# Schaltplan_Vier-Gewinnt.net
KiCad netlist of a schematic drawn in EasyEDA
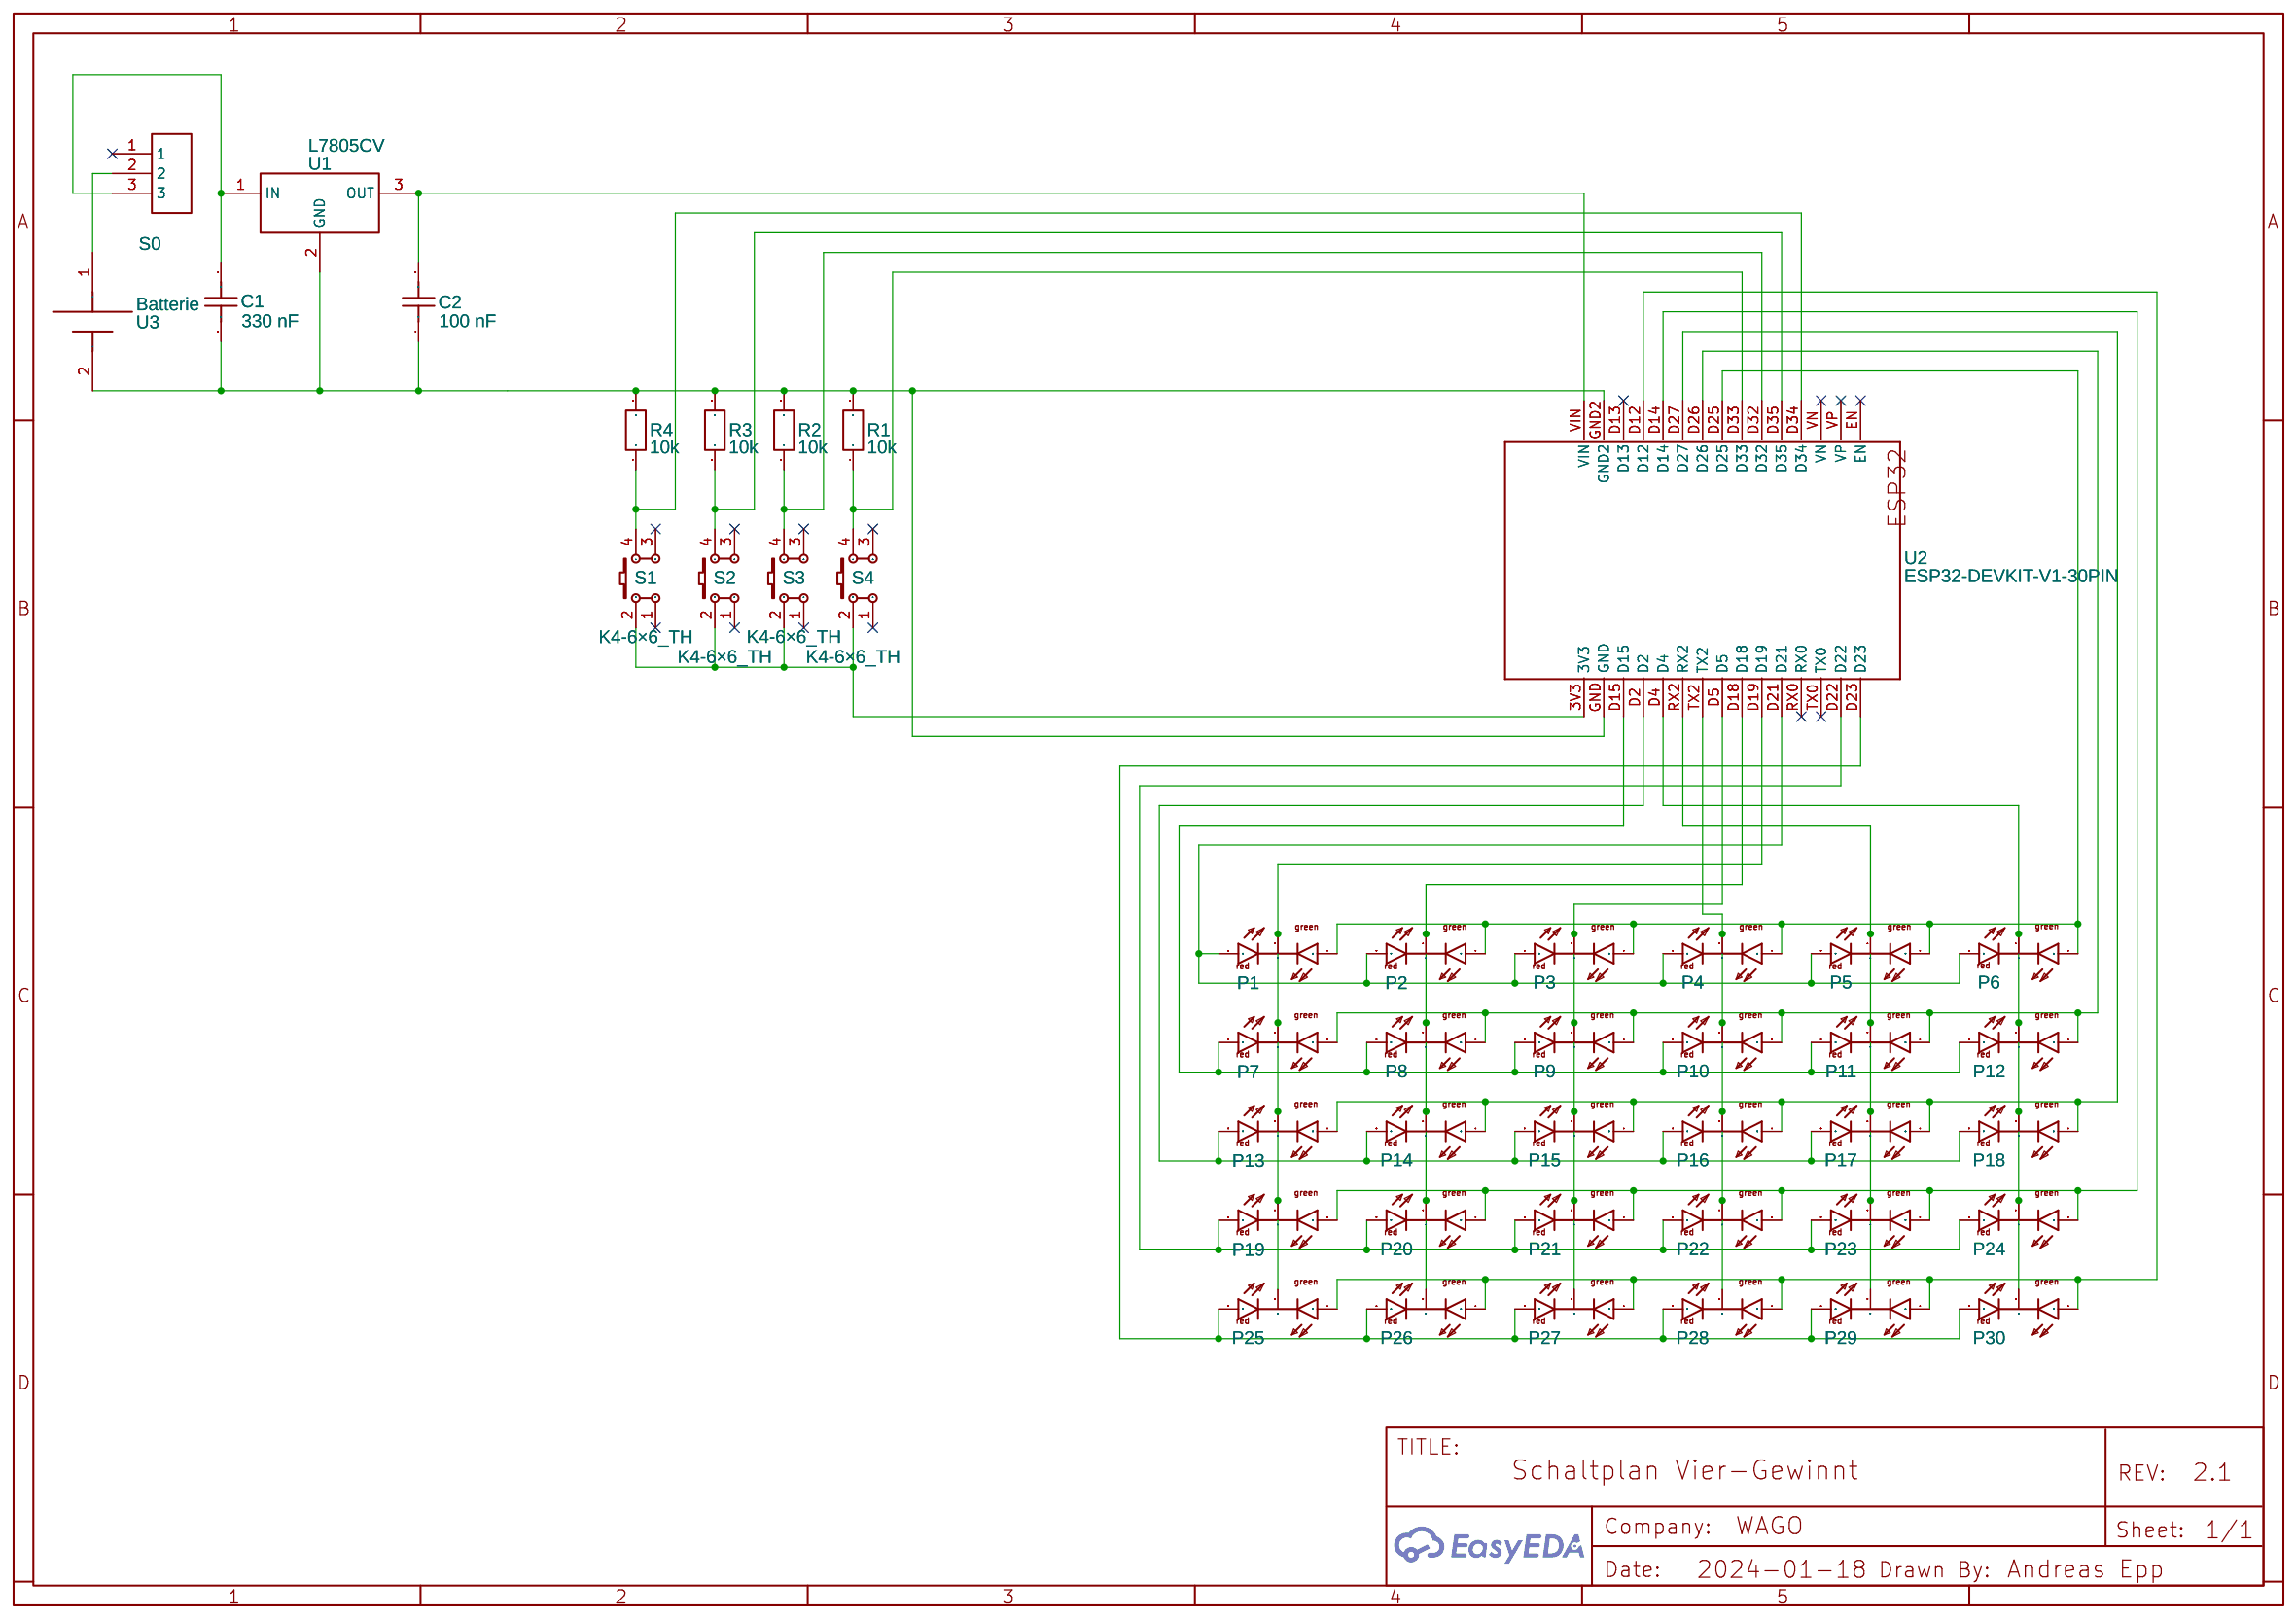
[diagram p0: schematic sheet]

(export (version "E")
  (design (tool "Eeschema 10.0.6"))
  (components
    (comp (ref "C1") (value "330 nF") (libsource (lib "") (part "C_RAD-0.1_US")))
    (comp (ref "C2")
      (value "100 nF")
      (fields (field (name "Manufacturer Part") "B32529C0104M289") (field (name "Manufacturer") "TDK"))
      (libsource (lib "") (part "B32529C0104M289"))
    )
    (comp (ref "P1") (value "NO") (libsource (lib "") (part "DUOLED-RG-C_1")))
    (comp (ref "P2") (value "NO") (libsource (lib "") (part "DUOLED-RG-C_1")))
    (comp (ref "P3") (value "NO") (libsource (lib "") (part "DUOLED-RG-C_1")))
    (comp (ref "P4") (value "NO") (libsource (lib "") (part "DUOLED-RG-C_1")))
    (comp (ref "P5") (value "NO") (libsource (lib "") (part "DUOLED-RG-C_1")))
    (comp (ref "P6") (value "NO") (libsource (lib "") (part "DUOLED-RG-C")))
    (comp (ref "P7") (value "NO") (libsource (lib "") (part "DUOLED-RG-C")))
    (comp (ref "P8") (value "NO") (libsource (lib "") (part "DUOLED-RG-C")))
    (comp (ref "P9") (value "NO") (libsource (lib "") (part "DUOLED-RG-C")))
    (comp (ref "P10") (value "NO") (libsource (lib "") (part "DUOLED-RG-C")))
    (comp (ref "P11") (value "NO") (libsource (lib "") (part "DUOLED-RG-C")))
    (comp (ref "P12") (value "NO") (libsource (lib "") (part "DUOLED-RG-C")))
    (comp (ref "P13") (value "NO") (libsource (lib "") (part "DUOLED-RG-C")))
    (comp (ref "P14") (value "NO") (libsource (lib "") (part "DUOLED-RG-C")))
    (comp (ref "P15") (value "NO") (libsource (lib "") (part "DUOLED-RG-C")))
    (comp (ref "P16") (value "NO") (libsource (lib "") (part "DUOLED-RG-C")))
    (comp (ref "P17") (value "NO") (libsource (lib "") (part "DUOLED-RG-C")))
    (comp (ref "P18") (value "NO") (libsource (lib "") (part "DUOLED-RG-C")))
    (comp (ref "P19") (value "NO") (libsource (lib "") (part "DUOLED-RG-C")))
    (comp (ref "P20") (value "NO") (libsource (lib "") (part "DUOLED-RG-C")))
    (comp (ref "P21") (value "NO") (libsource (lib "") (part "DUOLED-RG-C")))
    (comp (ref "P22") (value "NO") (libsource (lib "") (part "DUOLED-RG-C")))
    (comp (ref "P23") (value "NO") (libsource (lib "") (part "DUOLED-RG-C")))
    (comp (ref "P24") (value "NO") (libsource (lib "") (part "DUOLED-RG-C")))
    (comp (ref "P25") (value "NO") (libsource (lib "") (part "DUOLED-RG-C")))
    (comp (ref "P26") (value "NO") (libsource (lib "") (part "DUOLED-RG-C")))
    (comp (ref "P27") (value "NO") (libsource (lib "") (part "DUOLED-RG-C")))
    (comp (ref "P28") (value "NO") (libsource (lib "") (part "DUOLED-RG-C")))
    (comp (ref "P29") (value "NO") (libsource (lib "") (part "DUOLED-RG-C")))
    (comp (ref "P30") (value "NO") (libsource (lib "") (part "DUOLED-RG-C")))
    (comp (ref "R1") (value "10k") (libsource (lib "") (part "R_AXIAL-0.3_EU")))
    (comp (ref "R2") (value "10k") (libsource (lib "") (part "R_AXIAL-0.3_EU")))
    (comp (ref "R3") (value "10k") (libsource (lib "") (part "R_AXIAL-0.3_EU")))
    (comp (ref "R4") (value "10k") (libsource (lib "") (part "R_AXIAL-0.3_EU")))
    (comp (ref "S0") (value "NO") (libsource (lib "") (part "CSS-1201")))
    (comp (ref "S1")
      (value "K4-6×6_TH")
      (fields (field (name "Manufacturer Part") "K2-1102DP-E4SW-04") (field (name "Manufacturer") "韩国韩荣"))
      (libsource (lib "") (part "K4-6×6_TH"))
    )
    (comp (ref "S2")
      (value "K4-6×6_TH")
      (fields (field (name "Manufacturer Part") "K2-1102DP-E4SW-04") (field (name "Manufacturer") "韩国韩荣"))
      (libsource (lib "") (part "K4-6×6_TH"))
    )
    (comp (ref "S3")
      (value "K4-6×6_TH")
      (fields (field (name "Manufacturer Part") "K2-1102DP-E4SW-04") (field (name "Manufacturer") "韩国韩荣"))
      (libsource (lib "") (part "K4-6×6_TH"))
    )
    (comp (ref "S4")
      (value "K4-6×6_TH")
      (fields (field (name "Manufacturer Part") "K2-1102DP-E4SW-04") (field (name "Manufacturer") "韩国韩荣"))
      (libsource (lib "") (part "K4-6×6_TH"))
    )
    (comp (ref "U1")
      (value "L7805CV")
      (fields (field (name "Manufacturer") "STMicroelectronics"))
      (libsource (lib "") (part "L7805CV"))
    )
    (comp (ref "U2") (value "ESP32-DEVKIT-V1-30PIN") (libsource (lib "") (part "ESP32-DEVKIT-V1-30PIN")))
    (comp (ref "U3") (value "Batterie") (libsource (lib "") (part "Batterie")))
  )
  (nets
    (net (code "1") (name "Net-(P1-AG)") (class "Default")
      (node (ref "P1") (pin "AX") (pinfunction "AG_AX") (pintype "bidirectional"))
      (node (ref "P2") (pin "AX") (pinfunction "AG_AX") (pintype "bidirectional"))
      (node (ref "P3") (pin "AX") (pinfunction "AG_AX") (pintype "bidirectional"))
      (node (ref "P4") (pin "AX") (pinfunction "AG_AX") (pintype "bidirectional"))
      (node (ref "P5") (pin "AX") (pinfunction "AG_AX") (pintype "bidirectional"))
      (node (ref "P6") (pin "AX") (pinfunction "AG_AX") (pintype "bidirectional"))
      (node (ref "U2") (pin "D25") (pinfunction "D25_D25") (pintype "unspecified"))
    )
    (net (code "2") (name "Net-(P1-PadAR)") (class "Default")
      (node (ref "P1") (pin "AR") (pinfunction "AR_AR") (pintype "bidirectional"))
      (node (ref "P2") (pin "AR") (pinfunction "AR_AR") (pintype "bidirectional"))
      (node (ref "P3") (pin "AR") (pinfunction "AR_AR") (pintype "bidirectional"))
      (node (ref "P4") (pin "AR") (pinfunction "AR_AR") (pintype "bidirectional"))
      (node (ref "P5") (pin "AR") (pinfunction "AR_AR") (pintype "bidirectional"))
      (node (ref "P6") (pin "AR") (pinfunction "AR_AR") (pintype "bidirectional"))
      (node (ref "U2") (pin "D21") (pinfunction "D21_D21") (pintype "unspecified"))
    )
    (net (code "3") (name "Net-(P1-PadC)") (class "Default")
      (node (ref "P1") (pin "C") (pinfunction "C_C") (pintype "bidirectional"))
      (node (ref "P13") (pin "C") (pinfunction "C_C") (pintype "bidirectional"))
      (node (ref "P19") (pin "C") (pinfunction "C_C") (pintype "bidirectional"))
      (node (ref "P25") (pin "C") (pinfunction "C_C") (pintype "bidirectional"))
      (node (ref "P7") (pin "C") (pinfunction "C_C") (pintype "bidirectional"))
      (node (ref "U2") (pin "D19") (pinfunction "D19_D19") (pintype "unspecified"))
    )
    (net (code "4") (name "Net-(P10-AG)") (class "Default")
      (node (ref "P10") (pin "AX") (pinfunction "AG_AX") (pintype "bidirectional"))
      (node (ref "P11") (pin "AX") (pinfunction "AG_AX") (pintype "bidirectional"))
      (node (ref "P12") (pin "AX") (pinfunction "AG_AX") (pintype "bidirectional"))
      (node (ref "P7") (pin "AX") (pinfunction "AG_AX") (pintype "bidirectional"))
      (node (ref "P8") (pin "AX") (pinfunction "AG_AX") (pintype "bidirectional"))
      (node (ref "P9") (pin "AX") (pinfunction "AG_AX") (pintype "bidirectional"))
      (node (ref "U2") (pin "D26") (pinfunction "D26_D26") (pintype "unspecified"))
    )
    (net (code "5") (name "Net-(P10-PadAR)") (class "Default")
      (node (ref "P10") (pin "AR") (pinfunction "AR_AR") (pintype "bidirectional"))
      (node (ref "P11") (pin "AR") (pinfunction "AR_AR") (pintype "bidirectional"))
      (node (ref "P12") (pin "AR") (pinfunction "AR_AR") (pintype "bidirectional"))
      (node (ref "P7") (pin "AR") (pinfunction "AR_AR") (pintype "bidirectional"))
      (node (ref "P8") (pin "AR") (pinfunction "AR_AR") (pintype "bidirectional"))
      (node (ref "P9") (pin "AR") (pinfunction "AR_AR") (pintype "bidirectional"))
      (node (ref "U2") (pin "D15") (pinfunction "D15_D15") (pintype "unspecified"))
    )
    (net (code "6") (name "Net-(P10-PadC)") (class "Default")
      (node (ref "P10") (pin "C") (pinfunction "C_C") (pintype "bidirectional"))
      (node (ref "P16") (pin "C") (pinfunction "C_C") (pintype "bidirectional"))
      (node (ref "P22") (pin "C") (pinfunction "C_C") (pintype "bidirectional"))
      (node (ref "P28") (pin "C") (pinfunction "C_C") (pintype "bidirectional"))
      (node (ref "P4") (pin "C") (pinfunction "C_C") (pintype "bidirectional"))
      (node (ref "U2") (pin "TX2") (pinfunction "TX2_TX2") (pintype "unspecified"))
    )
    (net (code "7") (name "Net-(P11-PadC)") (class "Default")
      (node (ref "P11") (pin "C") (pinfunction "C_C") (pintype "bidirectional"))
      (node (ref "P17") (pin "C") (pinfunction "C_C") (pintype "bidirectional"))
      (node (ref "P23") (pin "C") (pinfunction "C_C") (pintype "bidirectional"))
      (node (ref "P29") (pin "C") (pinfunction "C_C") (pintype "bidirectional"))
      (node (ref "P5") (pin "C") (pinfunction "C_C") (pintype "bidirectional"))
      (node (ref "U2") (pin "RX2") (pinfunction "RX2_RX2") (pintype "unspecified"))
    )
    (net (code "8") (name "Net-(P12-PadC)") (class "Default")
      (node (ref "P12") (pin "C") (pinfunction "C_C") (pintype "bidirectional"))
      (node (ref "P18") (pin "C") (pinfunction "C_C") (pintype "bidirectional"))
      (node (ref "P24") (pin "C") (pinfunction "C_C") (pintype "bidirectional"))
      (node (ref "P30") (pin "C") (pinfunction "C_C") (pintype "bidirectional"))
      (node (ref "P6") (pin "C") (pinfunction "C_C") (pintype "bidirectional"))
      (node (ref "U2") (pin "D4") (pinfunction "D4_D4") (pintype "unspecified"))
    )
    (net (code "9") (name "Net-(P13-AG)") (class "Default")
      (node (ref "P13") (pin "AX") (pinfunction "AG_AX") (pintype "bidirectional"))
      (node (ref "P14") (pin "AX") (pinfunction "AG_AX") (pintype "bidirectional"))
      (node (ref "P15") (pin "AX") (pinfunction "AG_AX") (pintype "bidirectional"))
      (node (ref "P16") (pin "AX") (pinfunction "AG_AX") (pintype "bidirectional"))
      (node (ref "P17") (pin "AX") (pinfunction "AG_AX") (pintype "bidirectional"))
      (node (ref "P18") (pin "AX") (pinfunction "AG_AX") (pintype "bidirectional"))
      (node (ref "U2") (pin "D27") (pinfunction "D27_D27") (pintype "unspecified"))
    )
    (net (code "10") (name "Net-(P13-PadAR)") (class "Default")
      (node (ref "P13") (pin "AR") (pinfunction "AR_AR") (pintype "bidirectional"))
      (node (ref "P14") (pin "AR") (pinfunction "AR_AR") (pintype "bidirectional"))
      (node (ref "P15") (pin "AR") (pinfunction "AR_AR") (pintype "bidirectional"))
      (node (ref "P16") (pin "AR") (pinfunction "AR_AR") (pintype "bidirectional"))
      (node (ref "P17") (pin "AR") (pinfunction "AR_AR") (pintype "bidirectional"))
      (node (ref "P18") (pin "AR") (pinfunction "AR_AR") (pintype "bidirectional"))
      (node (ref "U2") (pin "D2") (pinfunction "D2_D2") (pintype "unspecified"))
    )
    (net (code "11") (name "Net-(P14-PadC)") (class "Default")
      (node (ref "P14") (pin "C") (pinfunction "C_C") (pintype "bidirectional"))
      (node (ref "P2") (pin "C") (pinfunction "C_C") (pintype "bidirectional"))
      (node (ref "P20") (pin "C") (pinfunction "C_C") (pintype "bidirectional"))
      (node (ref "P26") (pin "C") (pinfunction "C_C") (pintype "bidirectional"))
      (node (ref "P8") (pin "C") (pinfunction "C_C") (pintype "bidirectional"))
      (node (ref "U2") (pin "D18") (pinfunction "D18_D18") (pintype "unspecified"))
    )
    (net (code "12") (name "Net-(P15-PadC)") (class "Default")
      (node (ref "P15") (pin "C") (pinfunction "C_C") (pintype "bidirectional"))
      (node (ref "P21") (pin "C") (pinfunction "C_C") (pintype "bidirectional"))
      (node (ref "P27") (pin "C") (pinfunction "C_C") (pintype "bidirectional"))
      (node (ref "P3") (pin "C") (pinfunction "C_C") (pintype "bidirectional"))
      (node (ref "P9") (pin "C") (pinfunction "C_C") (pintype "bidirectional"))
      (node (ref "U2") (pin "D5") (pinfunction "D5_D5") (pintype "unspecified"))
    )
    (net (code "13") (name "Net-(P19-AG)") (class "Default")
      (node (ref "P19") (pin "AX") (pinfunction "AG_AX") (pintype "bidirectional"))
      (node (ref "P20") (pin "AX") (pinfunction "AG_AX") (pintype "bidirectional"))
      (node (ref "P21") (pin "AX") (pinfunction "AG_AX") (pintype "bidirectional"))
      (node (ref "P22") (pin "AX") (pinfunction "AG_AX") (pintype "bidirectional"))
      (node (ref "P23") (pin "AX") (pinfunction "AG_AX") (pintype "bidirectional"))
      (node (ref "P24") (pin "AX") (pinfunction "AG_AX") (pintype "bidirectional"))
      (node (ref "U2") (pin "D14") (pinfunction "D14_D14") (pintype "unspecified"))
    )
    (net (code "14") (name "Net-(P19-PadAR)") (class "Default")
      (node (ref "P19") (pin "AR") (pinfunction "AR_AR") (pintype "bidirectional"))
      (node (ref "P20") (pin "AR") (pinfunction "AR_AR") (pintype "bidirectional"))
      (node (ref "P21") (pin "AR") (pinfunction "AR_AR") (pintype "bidirectional"))
      (node (ref "P22") (pin "AR") (pinfunction "AR_AR") (pintype "bidirectional"))
      (node (ref "P23") (pin "AR") (pinfunction "AR_AR") (pintype "bidirectional"))
      (node (ref "P24") (pin "AR") (pinfunction "AR_AR") (pintype "bidirectional"))
      (node (ref "U2") (pin "D22") (pinfunction "D22_D22") (pintype "unspecified"))
    )
    (net (code "15") (name "Net-(P25-AG)") (class "Default")
      (node (ref "P25") (pin "AX") (pinfunction "AG_AX") (pintype "bidirectional"))
      (node (ref "P26") (pin "AX") (pinfunction "AG_AX") (pintype "bidirectional"))
      (node (ref "P27") (pin "AX") (pinfunction "AG_AX") (pintype "bidirectional"))
      (node (ref "P28") (pin "AX") (pinfunction "AG_AX") (pintype "bidirectional"))
      (node (ref "P29") (pin "AX") (pinfunction "AG_AX") (pintype "bidirectional"))
      (node (ref "P30") (pin "AX") (pinfunction "AG_AX") (pintype "bidirectional"))
      (node (ref "U2") (pin "D12") (pinfunction "D12_D12") (pintype "unspecified"))
    )
    (net (code "16") (name "Net-(P25-PadAR)") (class "Default")
      (node (ref "P25") (pin "AR") (pinfunction "AR_AR") (pintype "bidirectional"))
      (node (ref "P26") (pin "AR") (pinfunction "AR_AR") (pintype "bidirectional"))
      (node (ref "P27") (pin "AR") (pinfunction "AR_AR") (pintype "bidirectional"))
      (node (ref "P28") (pin "AR") (pinfunction "AR_AR") (pintype "bidirectional"))
      (node (ref "P29") (pin "AR") (pinfunction "AR_AR") (pintype "bidirectional"))
      (node (ref "P30") (pin "AR") (pinfunction "AR_AR") (pintype "bidirectional"))
      (node (ref "U2") (pin "D23") (pinfunction "D23_D23") (pintype "unspecified"))
    )
    (net (code "17") (name "Net-(R1-Pad1)") (class "Default")
      (node (ref "R1") (pin "1") (pinfunction "1_1") (pintype "unspecified"))
      (node (ref "S4") (pin "4") (pinfunction "4_4") (pintype "unspecified"))
      (node (ref "U2") (pin "D33") (pinfunction "D33_D33") (pintype "unspecified"))
    )
    (net (code "18") (name "Net-(R2-Pad1)") (class "Default")
      (node (ref "R2") (pin "1") (pinfunction "1_1") (pintype "unspecified"))
      (node (ref "S3") (pin "4") (pinfunction "4_4") (pintype "unspecified"))
      (node (ref "U2") (pin "D32") (pinfunction "D32_D32") (pintype "unspecified"))
    )
    (net (code "19") (name "Net-(R3-Pad1)") (class "Default")
      (node (ref "R3") (pin "1") (pinfunction "1_1") (pintype "unspecified"))
      (node (ref "S2") (pin "4") (pinfunction "4_4") (pintype "unspecified"))
      (node (ref "U2") (pin "D35") (pinfunction "D35_D35") (pintype "unspecified"))
    )
    (net (code "20") (name "Net-(R4-Pad1)") (class "Default")
      (node (ref "R4") (pin "1") (pinfunction "1_1") (pintype "unspecified"))
      (node (ref "S1") (pin "4") (pinfunction "4_4") (pintype "unspecified"))
      (node (ref "U2") (pin "D34") (pinfunction "D34_D34") (pintype "unspecified"))
    )
    (net (code "21") (name "Net-(S1-Pad2)") (class "Default")
      (node (ref "S1") (pin "2") (pinfunction "2_2") (pintype "unspecified"))
      (node (ref "S2") (pin "2") (pinfunction "2_2") (pintype "unspecified"))
      (node (ref "S3") (pin "2") (pinfunction "2_2") (pintype "unspecified"))
      (node (ref "S4") (pin "2") (pinfunction "2_2") (pintype "unspecified"))
      (node (ref "U2") (pin "3V3") (pinfunction "3V3_3V3") (pintype "unspecified"))
    )
    (net (code "22") (name "Net-(U1-GND)") (class "Default")
      (node (ref "C1") (pin "2") (pinfunction "2_2") (pintype "unspecified"))
      (node (ref "C2") (pin "1") (pinfunction "1_1") (pintype "unspecified"))
      (node (ref "R1") (pin "2") (pinfunction "2_2") (pintype "unspecified"))
      (node (ref "R2") (pin "2") (pinfunction "2_2") (pintype "unspecified"))
      (node (ref "R3") (pin "2") (pinfunction "2_2") (pintype "unspecified"))
      (node (ref "R4") (pin "2") (pinfunction "2_2") (pintype "unspecified"))
      (node (ref "U1") (pin "2") (pinfunction "GND_2") (pintype "unspecified"))
      (node (ref "U2") (pin "GND") (pinfunction "GND_GND") (pintype "unspecified"))
      (node (ref "U2") (pin "GND2") (pinfunction "GND2_GND2") (pintype "unspecified"))
      (node (ref "U3") (pin "2") (pinfunction "-_2") (pintype "unspecified"))
    )
    (net (code "23") (name "Net-(U1-IN)") (class "Default")
      (node (ref "C1") (pin "1") (pinfunction "1_1") (pintype "unspecified"))
      (node (ref "S0") (pin "3") (pinfunction "3_3") (pintype "unspecified"))
      (node (ref "U1") (pin "1") (pinfunction "IN_1") (pintype "unspecified"))
    )
    (net (code "24") (name "Net-(U1-OUT)") (class "Default")
      (node (ref "C2") (pin "2") (pinfunction "2_2") (pintype "unspecified"))
      (node (ref "U1") (pin "3") (pinfunction "OUT_3") (pintype "unspecified"))
      (node (ref "U2") (pin "VIN") (pinfunction "VIN_VIN") (pintype "unspecified"))
    )
    (net (code "25") (name "Net-(U3-+)") (class "Default")
      (node (ref "S0") (pin "2") (pinfunction "2_2") (pintype "unspecified"))
      (node (ref "U3") (pin "1") (pinfunction "+_1") (pintype "unspecified"))
    )
    (net (code "26") (name "unconnected-(S0-Pad1)") (class "Default")
      (node (ref "S0") (pin "1") (pinfunction "1_1") (pintype "unspecified+no_connect"))
    )
    (net (code "27") (name "unconnected-(S1-Pad1)") (class "Default")
      (node (ref "S1") (pin "1") (pinfunction "1_1") (pintype "unspecified+no_connect"))
    )
    (net (code "28") (name "unconnected-(S1-Pad3)") (class "Default")
      (node (ref "S1") (pin "3") (pinfunction "3_3") (pintype "unspecified+no_connect"))
    )
    (net (code "29") (name "unconnected-(S2-Pad1)") (class "Default")
      (node (ref "S2") (pin "1") (pinfunction "1_1") (pintype "unspecified+no_connect"))
    )
    (net (code "30") (name "unconnected-(S2-Pad3)") (class "Default")
      (node (ref "S2") (pin "3") (pinfunction "3_3") (pintype "unspecified+no_connect"))
    )
    (net (code "31") (name "unconnected-(S3-Pad1)") (class "Default")
      (node (ref "S3") (pin "1") (pinfunction "1_1") (pintype "unspecified+no_connect"))
    )
    (net (code "32") (name "unconnected-(S3-Pad3)") (class "Default")
      (node (ref "S3") (pin "3") (pinfunction "3_3") (pintype "unspecified+no_connect"))
    )
    (net (code "33") (name "unconnected-(S4-Pad1)") (class "Default")
      (node (ref "S4") (pin "1") (pinfunction "1_1") (pintype "unspecified+no_connect"))
    )
    (net (code "34") (name "unconnected-(S4-Pad3)") (class "Default")
      (node (ref "S4") (pin "3") (pinfunction "3_3") (pintype "unspecified+no_connect"))
    )
    (net (code "35") (name "unconnected-(U2-PadD13)") (class "Default")
      (node (ref "U2") (pin "D13") (pinfunction "D13_D13") (pintype "unspecified+no_connect"))
    )
    (net (code "36") (name "unconnected-(U2-PadEN)") (class "Default")
      (node (ref "U2") (pin "EN") (pinfunction "EN_EN") (pintype "unspecified+no_connect"))
    )
    (net (code "37") (name "unconnected-(U2-PadRX0)") (class "Default")
      (node (ref "U2") (pin "RX0") (pinfunction "RX0_RX0") (pintype "unspecified+no_connect"))
    )
    (net (code "38") (name "unconnected-(U2-PadTX0)") (class "Default")
      (node (ref "U2") (pin "TX0") (pinfunction "TX0_TX0") (pintype "unspecified+no_connect"))
    )
    (net (code "39") (name "unconnected-(U2-PadVN)") (class "Default")
      (node (ref "U2") (pin "VN") (pinfunction "VN_VN") (pintype "unspecified+no_connect"))
    )
    (net (code "40") (name "unconnected-(U2-PadVP)") (class "Default")
      (node (ref "U2") (pin "VP") (pinfunction "VP_VP") (pintype "unspecified+no_connect"))
    )
  )
)
